# Fishbot_transmitter.net
KiCad netlist of a schematic drawn in EAGLE
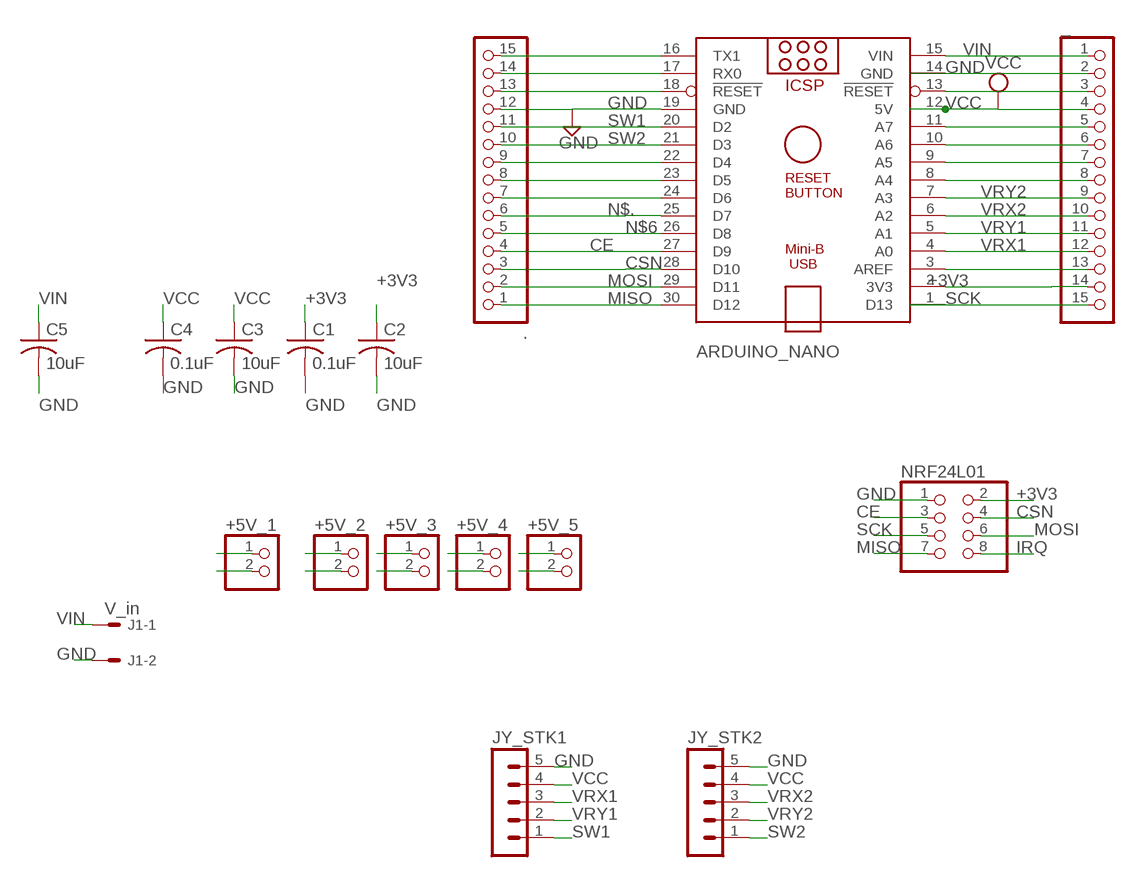
[diagram p0: schematic, sheet 1]

(export (version "E")
  (design (tool "Eeschema 10.0.6"))
  (components
    (comp (ref "+5V_1")
      (value "PINHD-1X2")
      (footprint "eagle-import:1X02")
      (libsource (lib "eagle-import") (part "PINHD-1X2"))
    )
    (comp (ref "+5V_2")
      (value "PINHD-1X2")
      (footprint "eagle-import:1X02")
      (libsource (lib "eagle-import") (part "PINHD-1X2"))
    )
    (comp (ref "+5V_3")
      (value "PINHD-1X2")
      (footprint "eagle-import:1X02")
      (libsource (lib "eagle-import") (part "PINHD-1X2"))
    )
    (comp (ref "+5V_4")
      (value "PINHD-1X2")
      (footprint "eagle-import:1X02")
      (libsource (lib "eagle-import") (part "PINHD-1X2"))
    )
    (comp (ref "+5V_5")
      (value "PINHD-1X2")
      (footprint "eagle-import:1X02")
      (libsource (lib "eagle-import") (part "PINHD-1X2"))
    )
    (comp (ref ".")
      (value "PINHD-1X15")
      (footprint "eagle-import:1X15")
      (libsource (lib "eagle-import") (part "PINHD-1X15"))
    )
    (comp (ref "ARDUINO_NANO")
      (value "ARDUINO_NANO")
      (footprint "eagle-import:ARDUINO_NANO")
      (libsource (lib "eagle-import") (part "ARDUINO_NANO"))
    )
    (comp (ref "C1")
      (value "0.1uF")
      (footprint "eagle-import:C1206")
      (libsource (lib "eagle-import") (part "C-USC1206"))
    )
    (comp (ref "C2")
      (value "10uF")
      (footprint "eagle-import:C1206")
      (libsource (lib "eagle-import") (part "C-USC1206"))
    )
    (comp (ref "C3")
      (value "10uF")
      (footprint "eagle-import:C1206")
      (libsource (lib "eagle-import") (part "C-USC1206"))
    )
    (comp (ref "C4")
      (value "0.1uF")
      (footprint "eagle-import:C1206")
      (libsource (lib "eagle-import") (part "C-USC1206"))
    )
    (comp (ref "C5")
      (value "10uF")
      (footprint "eagle-import:C1206")
      (libsource (lib "eagle-import") (part "C-USC1206"))
    )
    (comp (ref "J1")
      (value "V_in")
      (footprint "eagle-import:6410-02")
      (fields (field (name "MF") "MOLEX"))
      (libsource (lib "eagle-import") (part "22-?-0227-2021"))
    )
    (comp (ref "JY_STK1")
      (value "MA05-1")
      (footprint "eagle-import:MA05-1")
      (libsource (lib "eagle-import") (part "MA05-1"))
    )
    (comp (ref "JY_STK2")
      (value "MA05-1")
      (footprint "eagle-import:MA05-1")
      (libsource (lib "eagle-import") (part "MA05-1"))
    )
    (comp (ref "NRF24L01")
      (value "PINHD-2X4")
      (footprint "eagle-import:2X04")
      (libsource (lib "eagle-import") (part "PINHD-2X4"))
    )
    (comp (ref "_")
      (value "PINHD-1X15")
      (footprint "eagle-import:1X15")
      (libsource (lib "eagle-import") (part "PINHD-1X15"))
    )
  )
  (nets
    (net (code "1") (name "/+3V3") (class "Default")
      (node (ref "ARDUINO_NANO") (pin "2") (pinfunction "3V3_2") (pintype "output"))
      (node (ref "C1") (pin "1") (pinfunction "1_1") (pintype "passive"))
      (node (ref "C2") (pin "1") (pinfunction "1_1") (pintype "passive"))
      (node (ref "NRF24L01") (pin "2") (pinfunction "2_2") (pintype "passive"))
      (node (ref "_") (pin "14") (pinfunction "14_14") (pintype "passive"))
    )
    (net (code "2") (name "/CE") (class "Default")
      (node (ref ".") (pin "4") (pinfunction "4_4") (pintype "passive"))
      (node (ref "ARDUINO_NANO") (pin "27") (pinfunction "D9_27") (pintype "bidirectional"))
      (node (ref "NRF24L01") (pin "3") (pinfunction "3_3") (pintype "passive"))
    )
    (net (code "3") (name "/CSN") (class "Default")
      (node (ref ".") (pin "3") (pinfunction "3_3") (pintype "passive"))
      (node (ref "ARDUINO_NANO") (pin "28") (pinfunction "D10_28") (pintype "bidirectional"))
      (node (ref "NRF24L01") (pin "4") (pinfunction "4_4") (pintype "passive"))
    )
    (net (code "4") (name "/IRQ") (class "Default")
      (node (ref "NRF24L01") (pin "8") (pinfunction "8_8") (pintype "passive"))
    )
    (net (code "5") (name "/MISO") (class "Default")
      (node (ref ".") (pin "1") (pinfunction "1_1") (pintype "passive"))
      (node (ref "ARDUINO_NANO") (pin "30") (pinfunction "D12_30") (pintype "bidirectional"))
      (node (ref "NRF24L01") (pin "7") (pinfunction "7_7") (pintype "passive"))
    )
    (net (code "6") (name "/MOSI") (class "Default")
      (node (ref ".") (pin "2") (pinfunction "2_2") (pintype "passive"))
      (node (ref "ARDUINO_NANO") (pin "29") (pinfunction "D11_29") (pintype "bidirectional"))
      (node (ref "NRF24L01") (pin "6") (pinfunction "6_6") (pintype "passive"))
    )
    (net (code "7") (name "/N$.") (class "Default")
      (node (ref ".") (pin "6") (pinfunction "6_6") (pintype "passive"))
      (node (ref "ARDUINO_NANO") (pin "25") (pinfunction "D7_25") (pintype "bidirectional"))
    )
    (net (code "8") (name "/N$6") (class "Default")
      (node (ref ".") (pin "5") (pinfunction "5_5") (pintype "passive"))
      (node (ref "ARDUINO_NANO") (pin "26") (pinfunction "D8_26") (pintype "bidirectional"))
    )
    (net (code "9") (name "/SCK") (class "Default")
      (node (ref "ARDUINO_NANO") (pin "1") (pinfunction "D13_1") (pintype "bidirectional"))
      (node (ref "NRF24L01") (pin "5") (pinfunction "5_5") (pintype "passive"))
      (node (ref "_") (pin "15") (pinfunction "15_15") (pintype "passive"))
    )
    (net (code "10") (name "/SW1") (class "Default")
      (node (ref ".") (pin "11") (pinfunction "11_11") (pintype "passive"))
      (node (ref "ARDUINO_NANO") (pin "20") (pinfunction "D2_20") (pintype "bidirectional"))
      (node (ref "JY_STK1") (pin "1") (pinfunction "1_1") (pintype "passive"))
    )
    (net (code "11") (name "/SW2") (class "Default")
      (node (ref ".") (pin "10") (pinfunction "10_10") (pintype "passive"))
      (node (ref "ARDUINO_NANO") (pin "21") (pinfunction "D3_21") (pintype "bidirectional"))
      (node (ref "JY_STK2") (pin "1") (pinfunction "1_1") (pintype "passive"))
    )
    (net (code "12") (name "/VIN") (class "Default")
      (node (ref "ARDUINO_NANO") (pin "15") (pinfunction "VIN_15") (pintype "power_in"))
      (node (ref "C5") (pin "1") (pinfunction "1_1") (pintype "passive"))
      (node (ref "J1") (pin "1") (pinfunction "S_1") (pintype "passive"))
      (node (ref "_") (pin "1") (pinfunction "1_1") (pintype "passive"))
    )
    (net (code "13") (name "/VRX1") (class "Default")
      (node (ref "ARDUINO_NANO") (pin "4") (pinfunction "A0_4") (pintype "bidirectional"))
      (node (ref "JY_STK1") (pin "3") (pinfunction "3_3") (pintype "passive"))
      (node (ref "_") (pin "12") (pinfunction "12_12") (pintype "passive"))
    )
    (net (code "14") (name "/VRX2") (class "Default")
      (node (ref "ARDUINO_NANO") (pin "6") (pinfunction "A2_6") (pintype "bidirectional"))
      (node (ref "JY_STK2") (pin "3") (pinfunction "3_3") (pintype "passive"))
      (node (ref "_") (pin "10") (pinfunction "10_10") (pintype "passive"))
    )
    (net (code "15") (name "/VRY1") (class "Default")
      (node (ref "ARDUINO_NANO") (pin "5") (pinfunction "A1_5") (pintype "bidirectional"))
      (node (ref "JY_STK1") (pin "2") (pinfunction "2_2") (pintype "passive"))
      (node (ref "_") (pin "11") (pinfunction "11_11") (pintype "passive"))
    )
    (net (code "16") (name "/VRY2") (class "Default")
      (node (ref "ARDUINO_NANO") (pin "7") (pinfunction "A3_7") (pintype "bidirectional"))
      (node (ref "JY_STK2") (pin "2") (pinfunction "2_2") (pintype "passive"))
      (node (ref "_") (pin "9") (pinfunction "9_9") (pintype "passive"))
    )
    (net (code "17") (name "GND") (class "Default")
      (node (ref "+5V_1") (pin "2") (pinfunction "2_2") (pintype "passive"))
      (node (ref "+5V_2") (pin "2") (pinfunction "2_2") (pintype "passive"))
      (node (ref "+5V_3") (pin "2") (pinfunction "2_2") (pintype "passive"))
      (node (ref "+5V_4") (pin "2") (pinfunction "2_2") (pintype "passive"))
      (node (ref "+5V_5") (pin "2") (pinfunction "2_2") (pintype "passive"))
      (node (ref ".") (pin "12") (pinfunction "12_12") (pintype "passive"))
      (node (ref "ARDUINO_NANO") (pin "14") (pinfunction "GND_14") (pintype "power_in"))
      (node (ref "ARDUINO_NANO") (pin "19") (pinfunction "GND_19") (pintype "power_in"))
      (node (ref "C1") (pin "2") (pinfunction "2_2") (pintype "passive"))
      (node (ref "C2") (pin "2") (pinfunction "2_2") (pintype "passive"))
      (node (ref "C3") (pin "2") (pinfunction "2_2") (pintype "passive"))
      (node (ref "C4") (pin "2") (pinfunction "2_2") (pintype "passive"))
      (node (ref "C5") (pin "2") (pinfunction "2_2") (pintype "passive"))
      (node (ref "J1") (pin "2") (pinfunction "S_2") (pintype "passive"))
      (node (ref "JY_STK1") (pin "5") (pinfunction "5_5") (pintype "passive"))
      (node (ref "JY_STK2") (pin "5") (pinfunction "5_5") (pintype "passive"))
      (node (ref "NRF24L01") (pin "1") (pinfunction "1_1") (pintype "passive"))
      (node (ref "_") (pin "2") (pinfunction "2_2") (pintype "passive"))
    )
    (net (code "18") (name "Net-(.-Pad13)") (class "Default")
      (node (ref ".") (pin "13") (pinfunction "13_13") (pintype "passive"))
      (node (ref "ARDUINO_NANO") (pin "18") (pinfunction "~{RESET}_18") (pintype "input"))
    )
    (net (code "19") (name "Net-(ARDUINO_NANO-A4)") (class "Default")
      (node (ref "ARDUINO_NANO") (pin "8") (pinfunction "A4_8") (pintype "bidirectional"))
      (node (ref "_") (pin "8") (pinfunction "8_8") (pintype "passive"))
    )
    (net (code "20") (name "Net-(ARDUINO_NANO-A5)") (class "Default")
      (node (ref "ARDUINO_NANO") (pin "9") (pinfunction "A5_9") (pintype "bidirectional"))
      (node (ref "_") (pin "7") (pinfunction "7_7") (pintype "passive"))
    )
    (net (code "21") (name "Net-(ARDUINO_NANO-A6)") (class "Default")
      (node (ref "ARDUINO_NANO") (pin "10") (pinfunction "A6_10") (pintype "bidirectional"))
      (node (ref "_") (pin "6") (pinfunction "6_6") (pintype "passive"))
    )
    (net (code "22") (name "Net-(ARDUINO_NANO-A7)") (class "Default")
      (node (ref "ARDUINO_NANO") (pin "11") (pinfunction "A7_11") (pintype "bidirectional"))
      (node (ref "_") (pin "5") (pinfunction "5_5") (pintype "passive"))
    )
    (net (code "23") (name "Net-(ARDUINO_NANO-AREF)") (class "Default")
      (node (ref "ARDUINO_NANO") (pin "3") (pinfunction "AREF_3") (pintype "input"))
      (node (ref "_") (pin "13") (pinfunction "13_13") (pintype "passive"))
    )
    (net (code "24") (name "Net-(ARDUINO_NANO-D4)") (class "Default")
      (node (ref ".") (pin "9") (pinfunction "9_9") (pintype "passive"))
      (node (ref "ARDUINO_NANO") (pin "22") (pinfunction "D4_22") (pintype "bidirectional"))
    )
    (net (code "25") (name "Net-(ARDUINO_NANO-D5)") (class "Default")
      (node (ref ".") (pin "8") (pinfunction "8_8") (pintype "passive"))
      (node (ref "ARDUINO_NANO") (pin "23") (pinfunction "D5_23") (pintype "bidirectional"))
    )
    (net (code "26") (name "Net-(ARDUINO_NANO-D6)") (class "Default")
      (node (ref ".") (pin "7") (pinfunction "7_7") (pintype "passive"))
      (node (ref "ARDUINO_NANO") (pin "24") (pinfunction "D6_24") (pintype "bidirectional"))
    )
    (net (code "27") (name "Net-(ARDUINO_NANO-RX0)") (class "Default")
      (node (ref ".") (pin "14") (pinfunction "14_14") (pintype "passive"))
      (node (ref "ARDUINO_NANO") (pin "17") (pinfunction "RX0_17") (pintype "bidirectional"))
    )
    (net (code "28") (name "Net-(ARDUINO_NANO-TX1)") (class "Default")
      (node (ref ".") (pin "15") (pinfunction "15_15") (pintype "passive"))
      (node (ref "ARDUINO_NANO") (pin "16") (pinfunction "TX1_16") (pintype "bidirectional"))
    )
    (net (code "29") (name "Net-(ARDUINO_NANO-~{RESET}-Pad13)") (class "Default")
      (node (ref "ARDUINO_NANO") (pin "13") (pinfunction "~{RESET}_13") (pintype "input"))
      (node (ref "_") (pin "3") (pinfunction "3_3") (pintype "passive"))
    )
    (net (code "30") (name "VCC") (class "Default")
      (node (ref "+5V_1") (pin "1") (pinfunction "1_1") (pintype "passive"))
      (node (ref "+5V_2") (pin "1") (pinfunction "1_1") (pintype "passive"))
      (node (ref "+5V_3") (pin "1") (pinfunction "1_1") (pintype "passive"))
      (node (ref "+5V_4") (pin "1") (pinfunction "1_1") (pintype "passive"))
      (node (ref "+5V_5") (pin "1") (pinfunction "1_1") (pintype "passive"))
      (node (ref "ARDUINO_NANO") (pin "12") (pinfunction "5V_12") (pintype "power_in"))
      (node (ref "C3") (pin "1") (pinfunction "1_1") (pintype "passive"))
      (node (ref "C4") (pin "1") (pinfunction "1_1") (pintype "passive"))
      (node (ref "JY_STK1") (pin "4") (pinfunction "4_4") (pintype "passive"))
      (node (ref "JY_STK2") (pin "4") (pinfunction "4_4") (pintype "passive"))
      (node (ref "_") (pin "4") (pinfunction "4_4") (pintype "passive"))
    )
  )
)
